# top.net
KiCad netlist of a schematic drawn in Altium Designer
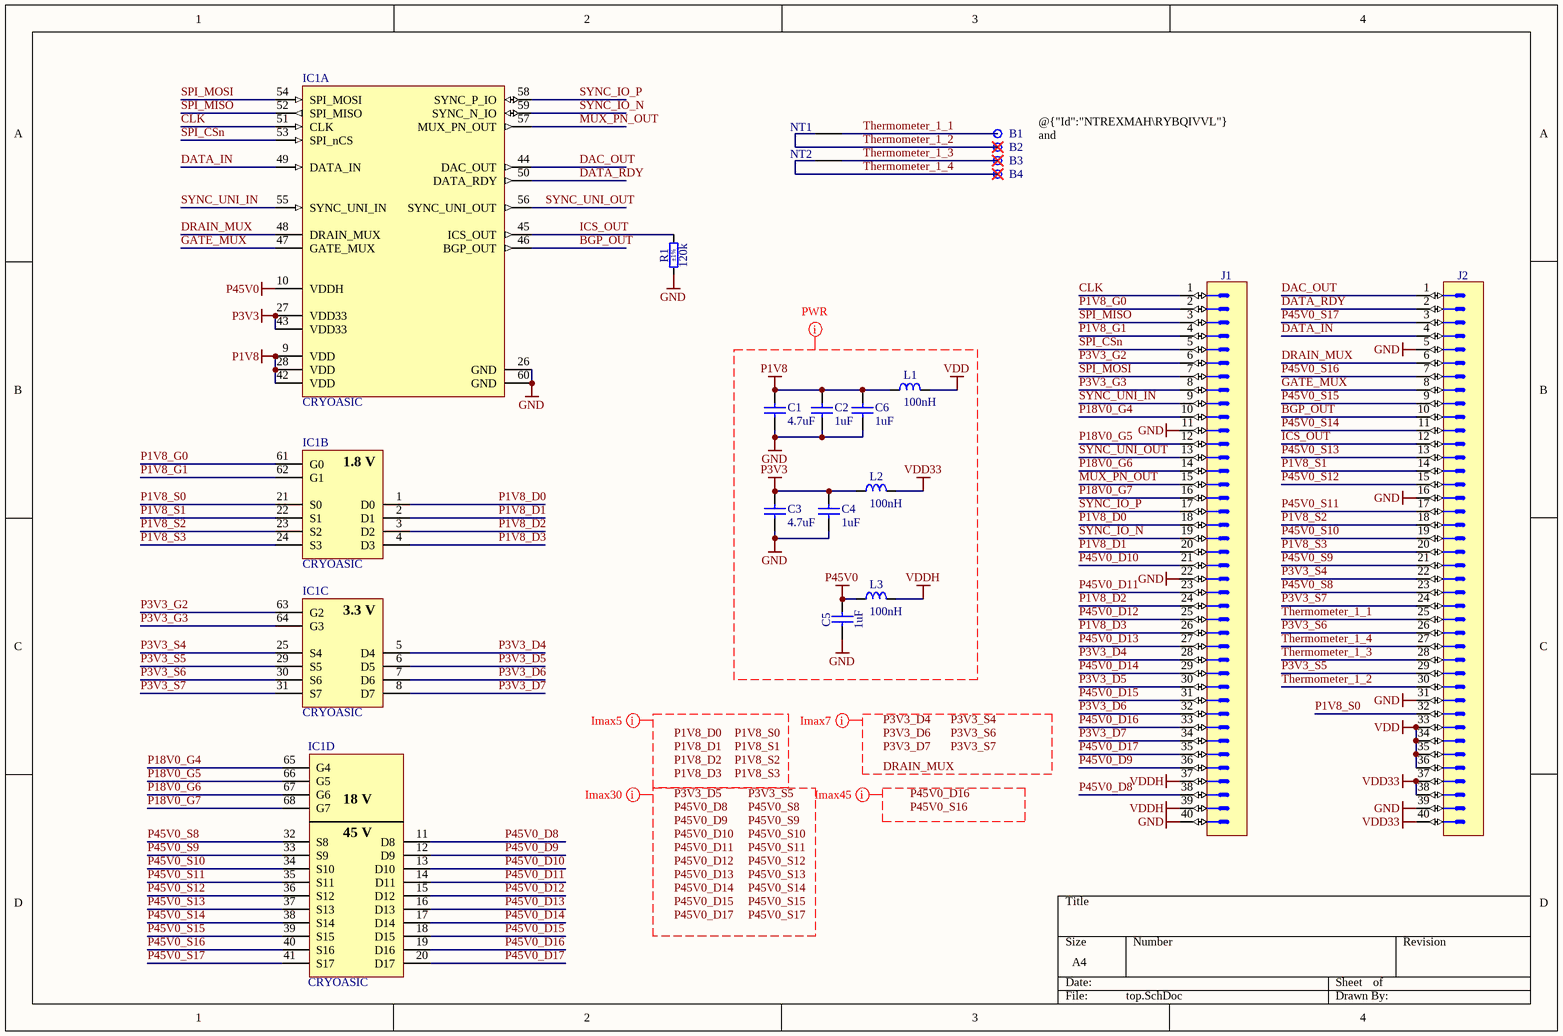
[diagram p0: top.SchDoc]

(export (version "E")
  (design (tool "Eeschema 10.0.6"))
  (components
    (comp (ref "B1")
      (value "Plated Hole")
      (footprint "c100h50")
      (description "Single Terminal Socket")
      (fields (field (name "PART NUMBER") "PLATED_HOLE0.5_PAD1.0") (field (name "AUTHOR") "CERN DEM JMW"))
      (libsource (lib "Eletro-mechanical") (part "Single Terminal Socket"))
    )
    (comp (ref "B2")
      (value "Plated Hole")
      (footprint "c100h50")
      (description "Single Terminal Socket")
      (fields (field (name "PART NUMBER") "PLATED_HOLE0.5_PAD1.0") (field (name "AUTHOR") "CERN DEM JMW"))
      (libsource (lib "Eletro-mechanical") (part "Single Terminal Socket"))
    )
    (comp (ref "B3")
      (value "Plated Hole")
      (footprint "c100h50")
      (description "Single Terminal Socket")
      (fields (field (name "PART NUMBER") "PLATED_HOLE0.5_PAD1.0") (field (name "AUTHOR") "CERN DEM JMW"))
      (libsource (lib "Eletro-mechanical") (part "Single Terminal Socket"))
    )
    (comp (ref "B4")
      (value "Plated Hole")
      (footprint "c100h50")
      (description "Single Terminal Socket")
      (fields (field (name "PART NUMBER") "PLATED_HOLE0.5_PAD1.0") (field (name "AUTHOR") "CERN DEM JMW"))
      (libsource (lib "Eletro-mechanical") (part "Single Terminal Socket"))
    )
    (comp (ref "C1")
      (value "4.7uF")
      (footprint "CAPC1005X55N")
      (description "Non-polarised capacitor")
      (fields
        (field (name "PART NUMBER") "CC0402_4.7UF_10V_10%_X5R")
        (field (name "VOLTAGE") "10V")
        (field (name "AUTHOR") "CERN DEM BC")
      )
      (libsource (lib "Capacitors") (part "Capacitor - non polarized"))
    )
    (comp (ref "C2")
      (value "1uF")
      (footprint "CAPC1005X55N")
      (description "Non-polarised capacitor")
      (fields
        (field (name "PART NUMBER") "CC0402_1UF_16V_10%_X5R")
        (field (name "VOLTAGE") "16V")
        (field (name "AUTHOR") "CERN DEM JLC")
      )
      (libsource (lib "Capacitors") (part "Capacitor - non polarized"))
    )
    (comp (ref "C3")
      (value "4.7uF")
      (footprint "CAPC1005X55N")
      (description "Non-polarised capacitor")
      (fields
        (field (name "PART NUMBER") "CC0402_4.7UF_10V_10%_X5R")
        (field (name "VOLTAGE") "10V")
        (field (name "AUTHOR") "CERN DEM BC")
      )
      (libsource (lib "Capacitors") (part "Capacitor - non polarized"))
    )
    (comp (ref "C4")
      (value "1uF")
      (footprint "CAPC1005X55N")
      (description "Non-polarised capacitor")
      (fields
        (field (name "PART NUMBER") "CC0402_1UF_16V_10%_X5R")
        (field (name "VOLTAGE") "16V")
        (field (name "AUTHOR") "CERN DEM JLC")
      )
      (libsource (lib "Capacitors") (part "Capacitor - non polarized"))
    )
    (comp (ref "C5")
      (value "1uF")
      (footprint "CAPC2013X145N")
      (description "Non-polarised capacitor")
      (fields
        (field (name "PART NUMBER") "CC0805_1UF_100V_10%_X7S")
        (field (name "VOLTAGE") "100V")
        (field (name "AUTHOR") "CERN DEM JLC")
      )
      (libsource (lib "Capacitors") (part "Capacitor - non polarized"))
    )
    (comp (ref "C6")
      (value "1uF")
      (footprint "CAPC1005X55N")
      (description "Non-polarised capacitor")
      (fields
        (field (name "PART NUMBER") "CC0402_1UF_16V_10%_X5R")
        (field (name "VOLTAGE") "16V")
        (field (name "AUTHOR") "CERN DEM JLC")
      )
      (libsource (lib "Capacitors") (part "Capacitor - non polarized"))
    )
    (comp (ref "IC1")
      (value "CRYOASIC")
      (footprint "FP-FJ0068A-IPC_A")
      (description "CRYOASIC_TEST1")
      (libsource (lib "CRYOASIC_TEST_LIB") (part "CRYOASIC"))
    )
    (comp (ref "J1")
      (value "Header 40")
      (footprint "SAMTEC_HDWM-20-54-L-D-335-SM-P")
      (description "Connector 40 Male")
      (fields
        (field (name "PART NUMBER") "SAMTEC_HDWM-20-54-L-D-335-SM-P")
        (field (name "MANUFACTURER") "SAMTEC")
        (field (name "AUTHOR") "CERN DEM JLC")
      )
      (libsource (lib "Connectors") (part "Connector 40 Male"))
    )
    (comp (ref "J2")
      (value "Header 40")
      (footprint "SAMTEC_HDWM-20-54-L-D-335-SM-P")
      (description "Connector 40 Male")
      (fields
        (field (name "PART NUMBER") "SAMTEC_HDWM-20-54-L-D-335-SM-P")
        (field (name "MANUFACTURER") "SAMTEC")
        (field (name "AUTHOR") "CERN DEM JLC")
      )
      (libsource (lib "Connectors") (part "Connector 40 Male"))
    )
    (comp (ref "L1")
      (value "100nH")
      (footprint "INDC1005X55N")
      (description "Inductor")
      (fields
        (field (name "PART NUMBER") "IND0402_100NH_5%_TDK_MLJ1005")
        (field (name "POWER") "400mA")
        (field (name "AUTHOR") "CERN DEM BC")
      )
      (libsource (lib "Inductors & Transformers") (part "Inductor"))
    )
    (comp (ref "L2")
      (value "100nH")
      (footprint "INDC1005X55N")
      (description "Inductor")
      (fields
        (field (name "PART NUMBER") "IND0402_100NH_5%_TDK_MLJ1005")
        (field (name "POWER") "400mA")
        (field (name "AUTHOR") "CERN DEM BC")
      )
      (libsource (lib "Inductors & Transformers") (part "Inductor"))
    )
    (comp (ref "L3")
      (value "100nH")
      (footprint "INDC1005X55N")
      (description "Inductor")
      (fields
        (field (name "PART NUMBER") "IND0402_100NH_5%_TDK_MLJ1005")
        (field (name "POWER") "400mA")
        (field (name "AUTHOR") "CERN DEM BC")
      )
      (libsource (lib "Inductors & Transformers") (part "Inductor"))
    )
    (comp (ref "NT1")
      (value "Net Tie")
      (footprint "Net Tie")
      (fields (field (name "AUTHOR") "CERN DEM JLC"))
      (libsource (lib "Eletro-mechanical") (part "Net Tie"))
    )
    (comp (ref "NT2")
      (value "Net Tie")
      (footprint "Net Tie")
      (fields (field (name "AUTHOR") "CERN DEM JLC"))
      (libsource (lib "Eletro-mechanical") (part "Net Tie"))
    )
    (comp (ref "R1")
      (value "120k")
      (footprint "RESC1005X40N")
      (description "Resistor - 1%")
      (fields
        (field (name "TOLERANCE") "±1%")
        (field (name "PART NUMBER") "R0402_120K_1%_0.0625W_100PPM")
        (field (name "POWER") "0.0625W")
        (field (name "AUTHOR") "CERN DEM JLC")
      )
      (libsource (lib "Resistors") (part "Resistor - 1%"))
    )
  )
  (nets
    (net (code "2") (name "/BGP_OUT") (class "Default")
      (node (ref "IC1") (pin "46") (pinfunction "BGP_OUT_46") (pintype "output"))
      (node (ref "J2") (pin "10") (pinfunction "10_10") (pintype "bidirectional"))
    )
    (net (code "3") (name "/CLK") (class "Default")
      (node (ref "IC1") (pin "51") (pinfunction "CLK_51") (pintype "input"))
      (node (ref "J1") (pin "1") (pinfunction "1_1") (pintype "bidirectional"))
    )
    (net (code "4") (name "/DAC_OUT") (class "Default")
      (node (ref "IC1") (pin "44") (pinfunction "DAC_OUT_44") (pintype "output"))
      (node (ref "J2") (pin "1") (pinfunction "1_1") (pintype "bidirectional"))
    )
    (net (code "5") (name "/DATA_IN") (class "Default")
      (node (ref "IC1") (pin "49") (pinfunction "DATA_IN_49") (pintype "input"))
      (node (ref "J2") (pin "4") (pinfunction "4_4") (pintype "bidirectional"))
    )
    (net (code "6") (name "/DATA_RDY") (class "Default")
      (node (ref "IC1") (pin "50") (pinfunction "DATA_RDY_50") (pintype "output"))
      (node (ref "J2") (pin "2") (pinfunction "2_2") (pintype "bidirectional"))
    )
    (net (code "7") (name "/DRAIN_MUX") (class "Default")
      (node (ref "IC1") (pin "48") (pinfunction "DRAIN_MUX_48") (pintype "passive"))
      (node (ref "J2") (pin "6") (pinfunction "6_6") (pintype "bidirectional"))
    )
    (net (code "8") (name "/GATE_MUX") (class "Default")
      (node (ref "IC1") (pin "47") (pinfunction "GATE_MUX_47") (pintype "passive"))
      (node (ref "J2") (pin "8") (pinfunction "8_8") (pintype "bidirectional"))
    )
    (net (code "9") (name "/ICS_OUT") (class "Default")
      (node (ref "IC1") (pin "45") (pinfunction "ICS_OUT_45") (pintype "output"))
      (node (ref "J2") (pin "12") (pinfunction "12_12") (pintype "bidirectional"))
      (node (ref "R1") (pin "2") (pinfunction "2_2") (pintype "passive"))
    )
    (net (code "10") (name "/MUX_PN_OUT") (class "Default")
      (node (ref "IC1") (pin "57") (pinfunction "MUX_PN_OUT_57") (pintype "output"))
      (node (ref "J1") (pin "15") (pinfunction "15_15") (pintype "bidirectional"))
    )
    (net (code "11") (name "/P1V8_D0") (class "Default")
      (node (ref "IC1") (pin "1") (pinfunction "D0_1") (pintype "passive"))
      (node (ref "J1") (pin "18") (pinfunction "18_18") (pintype "bidirectional"))
    )
    (net (code "12") (name "/P1V8_D1") (class "Default")
      (node (ref "IC1") (pin "2") (pinfunction "D1_2") (pintype "passive"))
      (node (ref "J1") (pin "20") (pinfunction "20_20") (pintype "bidirectional"))
    )
    (net (code "13") (name "/P1V8_D2") (class "Default")
      (node (ref "IC1") (pin "3") (pinfunction "D2_3") (pintype "passive"))
      (node (ref "J1") (pin "24") (pinfunction "24_24") (pintype "bidirectional"))
    )
    (net (code "14") (name "/P1V8_D3") (class "Default")
      (node (ref "IC1") (pin "4") (pinfunction "D3_4") (pintype "passive"))
      (node (ref "J1") (pin "26") (pinfunction "26_26") (pintype "bidirectional"))
    )
    (net (code "15") (name "/P1V8_G0") (class "Default")
      (node (ref "IC1") (pin "61") (pinfunction "G0_61") (pintype "passive"))
      (node (ref "J1") (pin "2") (pinfunction "2_2") (pintype "bidirectional"))
    )
    (net (code "16") (name "/P1V8_G1") (class "Default")
      (node (ref "IC1") (pin "62") (pinfunction "G1_62") (pintype "passive"))
      (node (ref "J1") (pin "4") (pinfunction "4_4") (pintype "bidirectional"))
    )
    (net (code "17") (name "/P1V8_S0") (class "Default")
      (node (ref "IC1") (pin "21") (pinfunction "S0_21") (pintype "passive"))
      (node (ref "J2") (pin "32") (pinfunction "32_32") (pintype "bidirectional"))
    )
    (net (code "18") (name "/P1V8_S1") (class "Default")
      (node (ref "IC1") (pin "22") (pinfunction "S1_22") (pintype "passive"))
      (node (ref "J2") (pin "14") (pinfunction "14_14") (pintype "bidirectional"))
    )
    (net (code "19") (name "/P1V8_S2") (class "Default")
      (node (ref "IC1") (pin "23") (pinfunction "S2_23") (pintype "passive"))
      (node (ref "J2") (pin "18") (pinfunction "18_18") (pintype "bidirectional"))
    )
    (net (code "20") (name "/P1V8_S3") (class "Default")
      (node (ref "IC1") (pin "24") (pinfunction "S3_24") (pintype "passive"))
      (node (ref "J2") (pin "20") (pinfunction "20_20") (pintype "bidirectional"))
    )
    (net (code "21") (name "/P3V3_D4") (class "Default")
      (node (ref "IC1") (pin "5") (pinfunction "D4_5") (pintype "passive"))
      (node (ref "J1") (pin "28") (pinfunction "28_28") (pintype "bidirectional"))
    )
    (net (code "22") (name "/P3V3_D5") (class "Default")
      (node (ref "IC1") (pin "6") (pinfunction "D5_6") (pintype "passive"))
      (node (ref "J1") (pin "30") (pinfunction "30_30") (pintype "bidirectional"))
    )
    (net (code "23") (name "/P3V3_D6") (class "Default")
      (node (ref "IC1") (pin "7") (pinfunction "D6_7") (pintype "passive"))
      (node (ref "J1") (pin "32") (pinfunction "32_32") (pintype "bidirectional"))
    )
    (net (code "24") (name "/P3V3_D7") (class "Default")
      (node (ref "IC1") (pin "8") (pinfunction "D7_8") (pintype "passive"))
      (node (ref "J1") (pin "34") (pinfunction "34_34") (pintype "bidirectional"))
    )
    (net (code "25") (name "/P3V3_G2") (class "Default")
      (node (ref "IC1") (pin "63") (pinfunction "G2_63") (pintype "passive"))
      (node (ref "J1") (pin "6") (pinfunction "6_6") (pintype "bidirectional"))
    )
    (net (code "26") (name "/P3V3_G3") (class "Default")
      (node (ref "IC1") (pin "64") (pinfunction "G3_64") (pintype "passive"))
      (node (ref "J1") (pin "8") (pinfunction "8_8") (pintype "bidirectional"))
    )
    (net (code "27") (name "/P3V3_S4") (class "Default")
      (node (ref "IC1") (pin "25") (pinfunction "S4_25") (pintype "passive"))
      (node (ref "J2") (pin "22") (pinfunction "22_22") (pintype "bidirectional"))
    )
    (net (code "28") (name "/P3V3_S5") (class "Default")
      (node (ref "IC1") (pin "29") (pinfunction "S5_29") (pintype "passive"))
      (node (ref "J2") (pin "29") (pinfunction "29_29") (pintype "bidirectional"))
    )
    (net (code "29") (name "/P3V3_S6") (class "Default")
      (node (ref "IC1") (pin "30") (pinfunction "S6_30") (pintype "passive"))
      (node (ref "J2") (pin "26") (pinfunction "26_26") (pintype "bidirectional"))
    )
    (net (code "30") (name "/P3V3_S7") (class "Default")
      (node (ref "IC1") (pin "31") (pinfunction "S7_31") (pintype "passive"))
      (node (ref "J2") (pin "24") (pinfunction "24_24") (pintype "bidirectional"))
    )
    (net (code "31") (name "/P18V0_G4") (class "Default")
      (node (ref "IC1") (pin "65") (pinfunction "G4_65") (pintype "passive"))
      (node (ref "J1") (pin "10") (pinfunction "10_10") (pintype "bidirectional"))
    )
    (net (code "32") (name "/P18V0_G5") (class "Default")
      (node (ref "IC1") (pin "66") (pinfunction "G5_66") (pintype "passive"))
      (node (ref "J1") (pin "12") (pinfunction "12_12") (pintype "bidirectional"))
    )
    (net (code "33") (name "/P18V0_G6") (class "Default")
      (node (ref "IC1") (pin "67") (pinfunction "G6_67") (pintype "passive"))
      (node (ref "J1") (pin "14") (pinfunction "14_14") (pintype "bidirectional"))
    )
    (net (code "34") (name "/P18V0_G7") (class "Default")
      (node (ref "IC1") (pin "68") (pinfunction "G7_68") (pintype "passive"))
      (node (ref "J1") (pin "16") (pinfunction "16_16") (pintype "bidirectional"))
    )
    (net (code "35") (name "/P45V0_D8") (class "Default")
      (node (ref "IC1") (pin "11") (pinfunction "D8_11") (pintype "passive"))
      (node (ref "J1") (pin "38") (pinfunction "38_38") (pintype "bidirectional"))
    )
    (net (code "36") (name "/P45V0_D9") (class "Default")
      (node (ref "IC1") (pin "12") (pinfunction "D9_12") (pintype "passive"))
      (node (ref "J1") (pin "36") (pinfunction "36_36") (pintype "bidirectional"))
    )
    (net (code "37") (name "/P45V0_D10") (class "Default")
      (node (ref "IC1") (pin "13") (pinfunction "D10_13") (pintype "passive"))
      (node (ref "J1") (pin "21") (pinfunction "21_21") (pintype "bidirectional"))
    )
    (net (code "38") (name "/P45V0_D11") (class "Default")
      (node (ref "IC1") (pin "14") (pinfunction "D11_14") (pintype "passive"))
      (node (ref "J1") (pin "23") (pinfunction "23_23") (pintype "bidirectional"))
    )
    (net (code "39") (name "/P45V0_D12") (class "Default")
      (node (ref "IC1") (pin "15") (pinfunction "D12_15") (pintype "passive"))
      (node (ref "J1") (pin "25") (pinfunction "25_25") (pintype "bidirectional"))
    )
    (net (code "40") (name "/P45V0_D13") (class "Default")
      (node (ref "IC1") (pin "16") (pinfunction "D13_16") (pintype "passive"))
      (node (ref "J1") (pin "27") (pinfunction "27_27") (pintype "bidirectional"))
    )
    (net (code "41") (name "/P45V0_D14") (class "Default")
      (node (ref "IC1") (pin "17") (pinfunction "D14_17") (pintype "passive"))
      (node (ref "J1") (pin "29") (pinfunction "29_29") (pintype "bidirectional"))
    )
    (net (code "42") (name "/P45V0_D15") (class "Default")
      (node (ref "IC1") (pin "18") (pinfunction "D15_18") (pintype "passive"))
      (node (ref "J1") (pin "31") (pinfunction "31_31") (pintype "bidirectional"))
    )
    (net (code "43") (name "/P45V0_D16") (class "Default")
      (node (ref "IC1") (pin "19") (pinfunction "D16_19") (pintype "passive"))
      (node (ref "J1") (pin "33") (pinfunction "33_33") (pintype "bidirectional"))
    )
    (net (code "44") (name "/P45V0_D17") (class "Default")
      (node (ref "IC1") (pin "20") (pinfunction "D17_20") (pintype "passive"))
      (node (ref "J1") (pin "35") (pinfunction "35_35") (pintype "bidirectional"))
    )
    (net (code "45") (name "/P45V0_S8") (class "Default")
      (node (ref "IC1") (pin "32") (pinfunction "S8_32") (pintype "passive"))
      (node (ref "J2") (pin "23") (pinfunction "23_23") (pintype "bidirectional"))
    )
    (net (code "46") (name "/P45V0_S9") (class "Default")
      (node (ref "IC1") (pin "33") (pinfunction "S9_33") (pintype "passive"))
      (node (ref "J2") (pin "21") (pinfunction "21_21") (pintype "bidirectional"))
    )
    (net (code "47") (name "/P45V0_S10") (class "Default")
      (node (ref "IC1") (pin "34") (pinfunction "S10_34") (pintype "passive"))
      (node (ref "J2") (pin "19") (pinfunction "19_19") (pintype "bidirectional"))
    )
    (net (code "48") (name "/P45V0_S11") (class "Default")
      (node (ref "IC1") (pin "35") (pinfunction "S11_35") (pintype "passive"))
      (node (ref "J2") (pin "17") (pinfunction "17_17") (pintype "bidirectional"))
    )
    (net (code "49") (name "/P45V0_S12") (class "Default")
      (node (ref "IC1") (pin "36") (pinfunction "S12_36") (pintype "passive"))
      (node (ref "J2") (pin "15") (pinfunction "15_15") (pintype "bidirectional"))
    )
    (net (code "50") (name "/P45V0_S13") (class "Default")
      (node (ref "IC1") (pin "37") (pinfunction "S13_37") (pintype "passive"))
      (node (ref "J2") (pin "13") (pinfunction "13_13") (pintype "bidirectional"))
    )
    (net (code "51") (name "/P45V0_S14") (class "Default")
      (node (ref "IC1") (pin "38") (pinfunction "S14_38") (pintype "passive"))
      (node (ref "J2") (pin "11") (pinfunction "11_11") (pintype "bidirectional"))
    )
    (net (code "52") (name "/P45V0_S15") (class "Default")
      (node (ref "IC1") (pin "39") (pinfunction "S15_39") (pintype "passive"))
      (node (ref "J2") (pin "9") (pinfunction "9_9") (pintype "bidirectional"))
    )
    (net (code "53") (name "/P45V0_S16") (class "Default")
      (node (ref "IC1") (pin "40") (pinfunction "S16_40") (pintype "passive"))
      (node (ref "J2") (pin "7") (pinfunction "7_7") (pintype "bidirectional"))
    )
    (net (code "54") (name "/P45V0_S17") (class "Default")
      (node (ref "IC1") (pin "41") (pinfunction "S17_41") (pintype "passive"))
      (node (ref "J2") (pin "3") (pinfunction "3_3") (pintype "bidirectional"))
    )
    (net (code "55") (name "/SPI_CSn") (class "Default")
      (node (ref "IC1") (pin "53") (pinfunction "SPI_nCS_53") (pintype "input"))
      (node (ref "J1") (pin "5") (pinfunction "5_5") (pintype "bidirectional"))
    )
    (net (code "56") (name "/SPI_MISO") (class "Default")
      (node (ref "IC1") (pin "52") (pinfunction "SPI_MISO_52") (pintype "output"))
      (node (ref "J1") (pin "3") (pinfunction "3_3") (pintype "bidirectional"))
    )
    (net (code "57") (name "/SPI_MOSI") (class "Default")
      (node (ref "IC1") (pin "54") (pinfunction "SPI_MOSI_54") (pintype "input"))
      (node (ref "J1") (pin "7") (pinfunction "7_7") (pintype "bidirectional"))
    )
    (net (code "58") (name "/SYNC_IO_N") (class "Default")
      (node (ref "IC1") (pin "59") (pinfunction "SYNC_N_IO_59") (pintype "bidirectional"))
      (node (ref "J1") (pin "19") (pinfunction "19_19") (pintype "bidirectional"))
    )
    (net (code "59") (name "/SYNC_IO_P") (class "Default")
      (node (ref "IC1") (pin "58") (pinfunction "SYNC_P_IO_58") (pintype "bidirectional"))
      (node (ref "J1") (pin "17") (pinfunction "17_17") (pintype "bidirectional"))
    )
    (net (code "60") (name "/SYNC_UNI_IN") (class "Default")
      (node (ref "IC1") (pin "55") (pinfunction "SYNC_UNI_IN_55") (pintype "input"))
      (node (ref "J1") (pin "9") (pinfunction "9_9") (pintype "bidirectional"))
    )
    (net (code "61") (name "/SYNC_UNI_OUT") (class "Default")
      (node (ref "IC1") (pin "56") (pinfunction "SYNC_UNI_OUT_56") (pintype "output"))
      (node (ref "J1") (pin "13") (pinfunction "13_13") (pintype "bidirectional"))
    )
    (net (code "62") (name "/Thermometer_1_1") (class "Default")
      (node (ref "B1") (pin "1") (pinfunction "1_1") (pintype "bidirectional"))
      (node (ref "J2") (pin "25") (pinfunction "25_25") (pintype "bidirectional"))
      (node (ref "NT1") (pin "2") (pinfunction "2_2") (pintype "bidirectional"))
    )
    (net (code "63") (name "/Thermometer_1_2") (class "Default")
      (node (ref "B2") (pin "1") (pinfunction "1_1") (pintype "bidirectional"))
      (node (ref "J2") (pin "30") (pinfunction "30_30") (pintype "bidirectional"))
      (node (ref "NT1") (pin "1") (pinfunction "1_1") (pintype "bidirectional"))
    )
    (net (code "64") (name "/Thermometer_1_3") (class "Default")
      (node (ref "B3") (pin "1") (pinfunction "1_1") (pintype "bidirectional"))
      (node (ref "J2") (pin "28") (pinfunction "28_28") (pintype "bidirectional"))
      (node (ref "NT2") (pin "2") (pinfunction "2_2") (pintype "bidirectional"))
    )
    (net (code "65") (name "/Thermometer_1_4") (class "Default")
      (node (ref "B4") (pin "1") (pinfunction "1_1") (pintype "bidirectional"))
      (node (ref "J2") (pin "27") (pinfunction "27_27") (pintype "bidirectional"))
      (node (ref "NT2") (pin "1") (pinfunction "1_1") (pintype "bidirectional"))
    )
    (net (code "66") (name "GND") (class "Default")
      (node (ref "C1") (pin "2") (pinfunction "2_2") (pintype "passive"))
      (node (ref "C2") (pin "2") (pinfunction "2_2") (pintype "passive"))
      (node (ref "C3") (pin "2") (pinfunction "2_2") (pintype "passive"))
      (node (ref "C4") (pin "2") (pinfunction "2_2") (pintype "passive"))
      (node (ref "C5") (pin "1") (pinfunction "1_1") (pintype "passive"))
      (node (ref "C6") (pin "2") (pinfunction "2_2") (pintype "passive"))
      (node (ref "IC1") (pin "26") (pinfunction "GND_26") (pintype "power_in"))
      (node (ref "IC1") (pin "60") (pinfunction "GND_60") (pintype "power_in"))
      (node (ref "J1") (pin "11") (pinfunction "11_11") (pintype "bidirectional"))
      (node (ref "J1") (pin "22") (pinfunction "22_22") (pintype "bidirectional"))
      (node (ref "J1") (pin "40") (pinfunction "40_40") (pintype "bidirectional"))
      (node (ref "J2") (pin "16") (pinfunction "16_16") (pintype "bidirectional"))
      (node (ref "J2") (pin "31") (pinfunction "31_31") (pintype "bidirectional"))
      (node (ref "J2") (pin "39") (pinfunction "39_39") (pintype "bidirectional"))
      (node (ref "J2") (pin "5") (pinfunction "5_5") (pintype "bidirectional"))
      (node (ref "R1") (pin "1") (pinfunction "1_1") (pintype "passive"))
    )
    (net (code "67") (name "P1V8") (class "Default")
      (node (ref "C1") (pin "1") (pinfunction "1_1") (pintype "passive"))
      (node (ref "C2") (pin "1") (pinfunction "1_1") (pintype "passive"))
      (node (ref "C6") (pin "1") (pinfunction "1_1") (pintype "passive"))
      (node (ref "IC1") (pin "28") (pinfunction "VDD_28") (pintype "power_in"))
      (node (ref "IC1") (pin "42") (pinfunction "VDD_42") (pintype "power_in"))
      (node (ref "IC1") (pin "9") (pinfunction "VDD_9") (pintype "power_in"))
      (node (ref "L1") (pin "1") (pinfunction "1_1") (pintype "passive"))
    )
    (net (code "68") (name "P3V3") (class "Default")
      (node (ref "C3") (pin "1") (pinfunction "1_1") (pintype "passive"))
      (node (ref "C4") (pin "1") (pinfunction "1_1") (pintype "passive"))
      (node (ref "IC1") (pin "27") (pinfunction "VDD33_27") (pintype "power_in"))
      (node (ref "IC1") (pin "43") (pinfunction "VDD33_43") (pintype "power_in"))
      (node (ref "L2") (pin "1") (pinfunction "1_1") (pintype "passive"))
    )
    (net (code "69") (name "P45V0") (class "Default")
      (node (ref "C5") (pin "2") (pinfunction "2_2") (pintype "passive"))
      (node (ref "IC1") (pin "10") (pinfunction "VDDH_10") (pintype "power_in"))
      (node (ref "L3") (pin "1") (pinfunction "1_1") (pintype "passive"))
    )
    (net (code "70") (name "VDD") (class "Default")
      (node (ref "J2") (pin "33") (pinfunction "33_33") (pintype "bidirectional"))
      (node (ref "J2") (pin "34") (pinfunction "34_34") (pintype "bidirectional"))
      (node (ref "J2") (pin "35") (pinfunction "35_35") (pintype "bidirectional"))
      (node (ref "J2") (pin "36") (pinfunction "36_36") (pintype "bidirectional"))
      (node (ref "L1") (pin "2") (pinfunction "2_2") (pintype "passive"))
    )
    (net (code "71") (name "VDD33") (class "Default")
      (node (ref "J2") (pin "37") (pinfunction "37_37") (pintype "bidirectional"))
      (node (ref "J2") (pin "38") (pinfunction "38_38") (pintype "bidirectional"))
      (node (ref "J2") (pin "40") (pinfunction "40_40") (pintype "bidirectional"))
      (node (ref "L2") (pin "2") (pinfunction "2_2") (pintype "passive"))
    )
    (net (code "72") (name "VDDH") (class "Default")
      (node (ref "J1") (pin "37") (pinfunction "37_37") (pintype "bidirectional"))
      (node (ref "J1") (pin "39") (pinfunction "39_39") (pintype "bidirectional"))
      (node (ref "L3") (pin "2") (pinfunction "2_2") (pintype "passive"))
    )
  )
)
